# Sheet1.net
KiCad netlist of a schematic drawn in Altium Designer
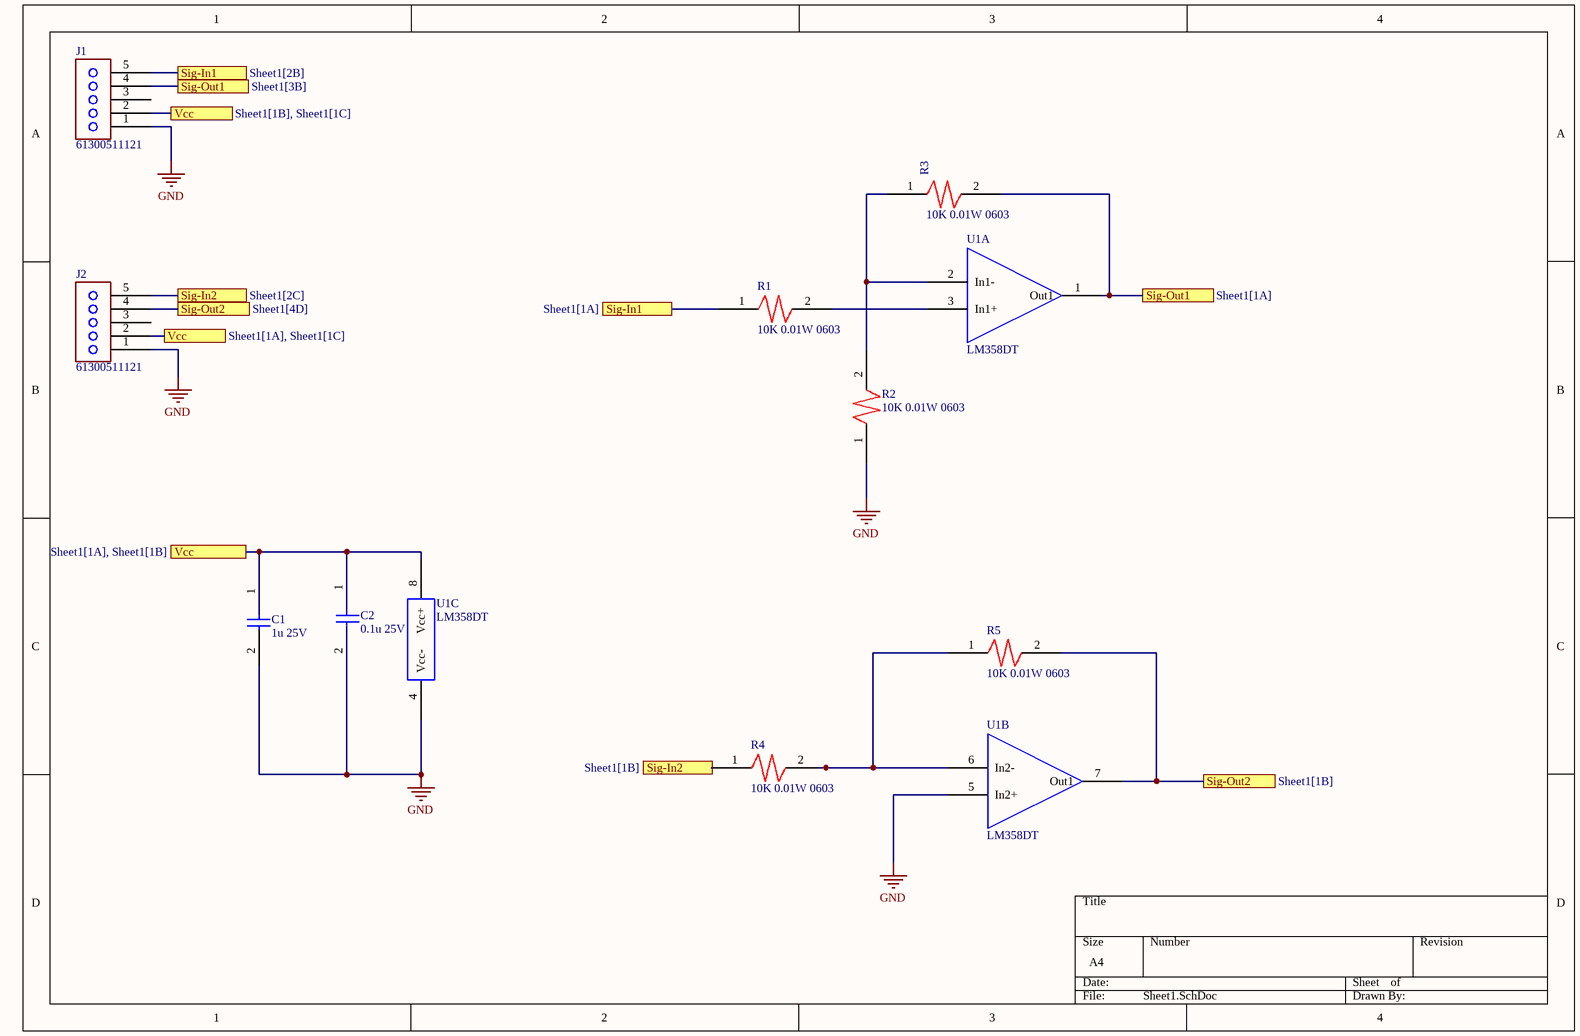
[diagram p0: Sheet1.SchDoc]

(export (version "E")
  (design (tool "Eeschema 10.0.6"))
  (components
    (comp (ref "C1")
      (value "1u 25V")
      (footprint "0603")
      (fields
        (field (name "MANUFACTURER") "Yageo")
        (field (name "MANUFACTURER PART NUMBER") "CC0603KRX5R8BB105")
      )
      (libsource (lib "Schlib1") (part "CC0603KRX5R8BB105"))
    )
    (comp (ref "C2")
      (value "0.1u 25V")
      (footprint "0603")
      (fields
        (field (name "MANUFACTURER") "Yageo")
        (field (name "MANUFACTURER PART NUMBER") "CC0603KRX7R8BB104")
      )
      (libsource (lib "Schlib1") (part "CC0603KRX7R8BB104"))
    )
    (comp (ref "J1")
      (value "61300511121")
      (footprint "HEADER-5PIN")
      (fields (field (name "MANUFACTURER") "Wurth Electronics"))
      (libsource (lib "Schlib1") (part "61300511121"))
    )
    (comp (ref "J2")
      (value "61300511121")
      (footprint "HEADER-5PIN")
      (fields (field (name "MANUFACTURER") "Wurth Electronics"))
      (libsource (lib "Schlib1") (part "61300511121"))
    )
    (comp (ref "R1")
      (value "10K 0.01W 0603")
      (footprint "0603")
      (fields
        (field (name "MANUFACTURER") "Yageo")
        (field (name "MANUFACTURER PART NUMBER") "RC0603FR-0710KL")
        (field (name "TOLERANCE") "1%")
      )
      (libsource (lib "Schlib1") (part "RC0603FR-0710KL"))
    )
    (comp (ref "R2")
      (value "10K 0.01W 0603")
      (footprint "0603")
      (fields
        (field (name "MANUFACTURER") "Yageo")
        (field (name "MANUFACTURER PART NUMBER") "RC0603FR-0710KL")
        (field (name "TOLERANCE") "1%")
      )
      (libsource (lib "Schlib1") (part "RC0603FR-0710KL"))
    )
    (comp (ref "R3")
      (value "10K 0.01W 0603")
      (footprint "0603")
      (fields
        (field (name "MANUFACTURER") "Yageo")
        (field (name "MANUFACTURER PART NUMBER") "RC0603FR-0710KL")
        (field (name "TOLERANCE") "1%")
      )
      (libsource (lib "Schlib1") (part "RC0603FR-0710KL"))
    )
    (comp (ref "R4")
      (value "10K 0.01W 0603")
      (footprint "0603")
      (fields
        (field (name "MANUFACTURER") "Yageo")
        (field (name "MANUFACTURER PART NUMBER") "RC0603FR-0710KL")
        (field (name "TOLERANCE") "1%")
      )
      (libsource (lib "Schlib1") (part "RC0603FR-0710KL"))
    )
    (comp (ref "R5")
      (value "10K 0.01W 0603")
      (footprint "0603")
      (fields
        (field (name "MANUFACTURER") "Yageo")
        (field (name "MANUFACTURER PART NUMBER") "RC0603FR-0710KL")
        (field (name "TOLERANCE") "1%")
      )
      (libsource (lib "Schlib1") (part "RC0603FR-0710KL"))
    )
    (comp (ref "U1")
      (value "LM358DT")
      (footprint "8SOIC")
      (description "Operational Amplifier, 2 Func, 9000uV Offset-Max, BIPolar, PDSO8")
      (fields (field (name "MANUFACTURER") "STMicroelectronics"))
      (libsource (lib "Schlib1") (part "LM358DT"))
    )
  )
  (nets
    (net (code "1") (name "/Sig-In1") (class "Default")
      (node (ref "J1") (pin "5") (pintype "passive"))
      (node (ref "R1") (pin "1") (pintype "passive"))
    )
    (net (code "2") (name "/Sig-In2") (class "Default")
      (node (ref "J2") (pin "5") (pintype "passive"))
      (node (ref "R4") (pin "1") (pintype "passive"))
    )
    (net (code "3") (name "/Sig-Out1") (class "Default")
      (node (ref "J1") (pin "4") (pintype "passive"))
      (node (ref "R3") (pin "2") (pintype "passive"))
      (node (ref "U1") (pin "1") (pinfunction "Out1_1") (pintype "passive"))
    )
    (net (code "4") (name "/Sig-Out2") (class "Default")
      (node (ref "J2") (pin "4") (pintype "passive"))
      (node (ref "R5") (pin "2") (pintype "passive"))
      (node (ref "U1") (pin "7") (pinfunction "Out1_7") (pintype "passive"))
    )
    (net (code "5") (name "/Vcc") (class "Default")
      (node (ref "C1") (pin "1") (pintype "passive"))
      (node (ref "C2") (pin "1") (pintype "passive"))
      (node (ref "J1") (pin "2") (pintype "passive"))
      (node (ref "J2") (pin "2") (pintype "passive"))
      (node (ref "U1") (pin "8") (pinfunction "Vcc+_8") (pintype "passive"))
    )
    (net (code "6") (name "GND") (class "Default")
      (node (ref "C2") (pin "2") (pintype "passive"))
      (node (ref "J1") (pin "1") (pintype "passive"))
      (node (ref "J2") (pin "1") (pintype "passive"))
      (node (ref "R2") (pin "1") (pintype "passive"))
      (node (ref "U1") (pin "4") (pinfunction "Vcc-_4") (pintype "passive"))
      (node (ref "U1") (pin "5") (pinfunction "In2+_5") (pintype "passive"))
    )
    (net (code "7") (name "Net-(U1A-In1+)") (class "Default")
      (node (ref "R1") (pin "2") (pintype "passive"))
      (node (ref "U1") (pin "3") (pinfunction "In1+_3") (pintype "passive"))
    )
    (net (code "8") (name "Net-(U1A-In1-)") (class "Default")
      (node (ref "R2") (pin "2") (pintype "passive"))
      (node (ref "R3") (pin "1") (pintype "passive"))
      (node (ref "U1") (pin "2") (pinfunction "In1-_2") (pintype "passive"))
    )
    (net (code "9") (name "Net-(U1B-In2-)") (class "Default")
      (node (ref "R4") (pin "2") (pintype "passive"))
      (node (ref "R5") (pin "1") (pintype "passive"))
      (node (ref "U1") (pin "6") (pinfunction "In2-_6") (pintype "passive"))
    )
    (net (code "10") (name "unconnected-(C1-Pad2)") (class "Default")
      (node (ref "C1") (pin "2") (pintype "passive"))
    )
    (net (code "11") (name "unconnected-(J1-Pad3)") (class "Default")
      (node (ref "J1") (pin "3") (pintype "passive"))
    )
    (net (code "12") (name "unconnected-(J2-Pad3)") (class "Default")
      (node (ref "J2") (pin "3") (pintype "passive"))
    )
  )
)
